# USB_Host_Hub_TypeC_DRP.net
KiCad netlist of a schematic drawn in Altium Designer
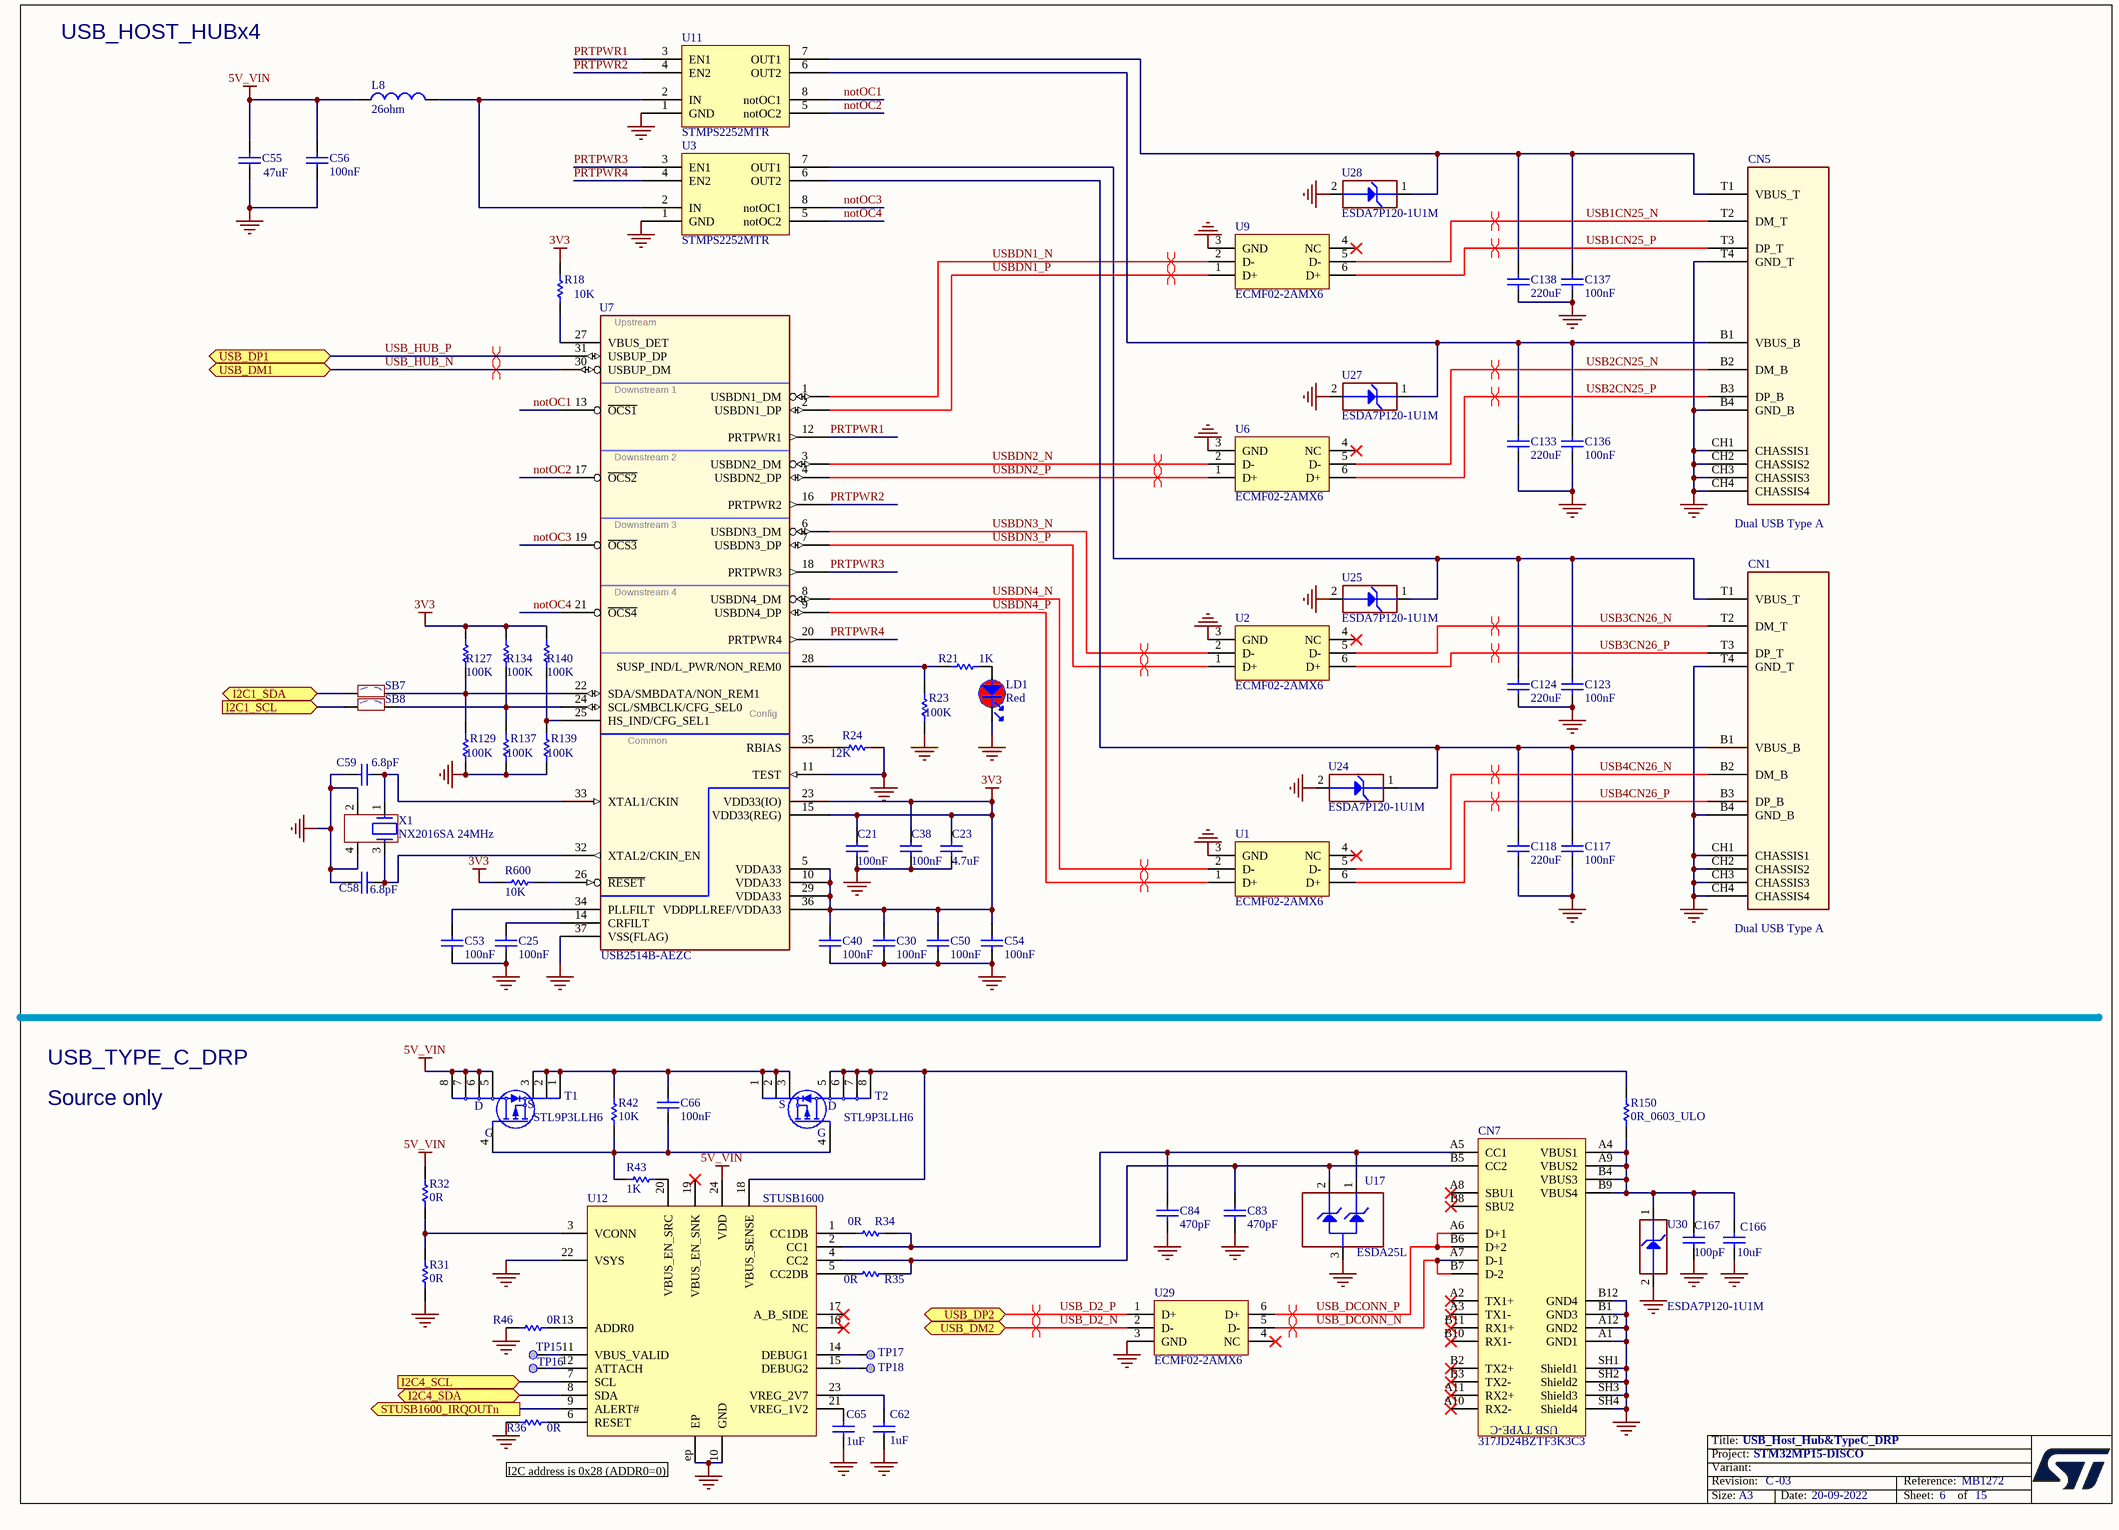
[diagram p0: USB_Host_Hub&TypeC_DRP.SchDoc]

(export (version "E")
  (design (tool "Eeschema 10.0.6"))
  (components
    (comp (ref "C21")
      (value "100nF")
      (footprint "C0402")
      (description "Capacitor, MLCC, 100nF, 16V, X7R, +/-10%, 0402, T=0.5mm")
      (fields
        (field (name "INTERNAL_PART_NUMBER") "MCD-00006")
        (field (name "MANUFACTURER_PART_NUMBER") "CC0402KRX7R7BB104")
      )
      (libsource (lib "MCD_PARTS_database") (part "Capacitor"))
    )
    (comp (ref "C23")
      (value "4.7uF")
      (footprint "C0402")
      (description "Capacitor, MLCC, 4.7uF, 6V3, X5R, 20%, 0402, T=0,5mm")
      (fields
        (field (name "INTERNAL_PART_NUMBER") "MCD-01356")
        (field (name "MANUFACTURER_PART_NUMBER") "GRM155R60J475ME47")
        (field (name "PROVIDED_BY") "SUBCO")
      )
      (libsource (lib "MCD_PARTS_database") (part "Capacitor"))
    )
    (comp (ref "C25")
      (value "100nF")
      (footprint "C0402")
      (description "Capacitor, MLCC, 100nF, 16V, X7R, +/-10%, 0402, T=0.5mm")
      (fields
        (field (name "INTERNAL_PART_NUMBER") "MCD-00006")
        (field (name "MANUFACTURER_PART_NUMBER") "CC0402KRX7R7BB104")
      )
      (libsource (lib "MCD_PARTS_database") (part "Capacitor"))
    )
    (comp (ref "C30")
      (value "100nF")
      (footprint "C0402")
      (description "Capacitor, MLCC, 100nF, 16V, X7R, +/-10%, 0402, T=0.5mm")
      (fields
        (field (name "INTERNAL_PART_NUMBER") "MCD-00006")
        (field (name "MANUFACTURER_PART_NUMBER") "CC0402KRX7R7BB104")
      )
      (libsource (lib "MCD_PARTS_database") (part "Capacitor"))
    )
    (comp (ref "C38")
      (value "100nF")
      (footprint "C0402")
      (description "Capacitor, MLCC, 100nF, 16V, X7R, +/-10%, 0402, T=0.5mm")
      (fields
        (field (name "INTERNAL_PART_NUMBER") "MCD-00006")
        (field (name "MANUFACTURER_PART_NUMBER") "CC0402KRX7R7BB104")
      )
      (libsource (lib "MCD_PARTS_database") (part "Capacitor"))
    )
    (comp (ref "C40")
      (value "100nF")
      (footprint "C0402")
      (description "Capacitor, MLCC, 100nF, 16V, X7R, +/-10%, 0402, T=0.5mm")
      (fields
        (field (name "INTERNAL_PART_NUMBER") "MCD-00006")
        (field (name "MANUFACTURER_PART_NUMBER") "CC0402KRX7R7BB104")
      )
      (libsource (lib "MCD_PARTS_database") (part "Capacitor"))
    )
    (comp (ref "C50")
      (value "100nF")
      (footprint "C0402")
      (description "Capacitor, MLCC, 100nF, 16V, X7R, +/-10%, 0402, T=0.5mm")
      (fields
        (field (name "INTERNAL_PART_NUMBER") "MCD-00006")
        (field (name "MANUFACTURER_PART_NUMBER") "CC0402KRX7R7BB104")
      )
      (libsource (lib "MCD_PARTS_database") (part "Capacitor"))
    )
    (comp (ref "C53")
      (value "100nF")
      (footprint "C0402")
      (description "Capacitor, MLCC, 100nF, 16V, X7R, +/-10%, 0402, T=0.5mm")
      (fields
        (field (name "INTERNAL_PART_NUMBER") "MCD-00006")
        (field (name "MANUFACTURER_PART_NUMBER") "CC0402KRX7R7BB104")
      )
      (libsource (lib "MCD_PARTS_database") (part "Capacitor"))
    )
    (comp (ref "C54")
      (value "100nF")
      (footprint "C0402")
      (description "Capacitor, MLCC, 100nF, 16V, X7R, +/-10%, 0402, T=0.5mm")
      (fields
        (field (name "INTERNAL_PART_NUMBER") "MCD-00006")
        (field (name "MANUFACTURER_PART_NUMBER") "CC0402KRX7R7BB104")
      )
      (libsource (lib "MCD_PARTS_database") (part "Capacitor"))
    )
    (comp (ref "C55")
      (value "47uF")
      (footprint "C0805")
      (description "Capacitor, MLCC, 47uF, 10V, X5R, 20%, 0805, T=1,25mm")
      (fields
        (field (name "INTERNAL_PART_NUMBER") "MCD-00204")
        (field (name "MANUFACTURER_PART_NUMBER") "GRM21BR61A476ME15K")
        (field (name "PROVIDED_BY") "SUBCO")
      )
      (libsource (lib "MCD_PARTS_database") (part "Capacitor"))
    )
    (comp (ref "C56")
      (value "100nF")
      (footprint "C0402")
      (description "Capacitor, MLCC, 100nF, 16V, X7R, +/-10%, 0402, T=0.5mm")
      (fields
        (field (name "INTERNAL_PART_NUMBER") "MCD-00006")
        (field (name "MANUFACTURER_PART_NUMBER") "CC0402KRX7R7BB104")
      )
      (libsource (lib "MCD_PARTS_database") (part "Capacitor"))
    )
    (comp (ref "C58")
      (value "6.8pF")
      (footprint "C0402")
      (description "Capacitor, MLCC, 6.8pF, 50V, NPO, +-0.25pF, 0402, T=0.5mm")
      (fields
        (field (name "INTERNAL_PART_NUMBER") "MCD-00674")
        (field (name "MANUFACTURER_PART_NUMBER") "CC0402CRNPO9BN6R8")
        (field (name "PROVIDED_BY") "SUBCO")
      )
      (libsource (lib "MCD_PARTS_database") (part "Capacitor"))
    )
    (comp (ref "C59")
      (value "6.8pF")
      (footprint "C0402")
      (description "Capacitor, MLCC, 6.8pF, 50V, NPO, +-0.25pF, 0402, T=0.5mm")
      (fields
        (field (name "INTERNAL_PART_NUMBER") "MCD-00674")
        (field (name "MANUFACTURER_PART_NUMBER") "CC0402CRNPO9BN6R8")
        (field (name "PROVIDED_BY") "SUBCO")
      )
      (libsource (lib "MCD_PARTS_database") (part "Capacitor"))
    )
    (comp (ref "C62")
      (value "1uF")
      (footprint "C0402")
      (description "Capacitor, MLCC, 1uF, 6V3, X5R, 10%, 0402, T=0,5mm")
      (fields
        (field (name "INTERNAL_PART_NUMBER") "MCD-00095")
        (field (name "MANUFACTURER_PART_NUMBER") "GRM155R61E105KA12")
        (field (name "PROVIDED_BY") "SUBCO")
      )
      (libsource (lib "MCD_PARTS_database") (part "Capacitor"))
    )
    (comp (ref "C65")
      (value "1uF")
      (footprint "C0402")
      (description "Capacitor, MLCC, 1uF, 6V3, X5R, 10%, 0402, T=0,5mm")
      (fields
        (field (name "INTERNAL_PART_NUMBER") "MCD-00095")
        (field (name "MANUFACTURER_PART_NUMBER") "GRM155R61E105KA12")
        (field (name "PROVIDED_BY") "SUBCO")
      )
      (libsource (lib "MCD_PARTS_database") (part "Capacitor"))
    )
    (comp (ref "C66")
      (value "100nF")
      (footprint "C0402")
      (description "Capacitor, MLCC, 100nF, 16V, X7R, +/-10%, 0402, T=0.5mm")
      (fields
        (field (name "INTERNAL_PART_NUMBER") "MCD-00006")
        (field (name "MANUFACTURER_PART_NUMBER") "CC0402KRX7R7BB104")
      )
      (libsource (lib "MCD_PARTS_database") (part "Capacitor"))
    )
    (comp (ref "C83")
      (value "470pF")
      (footprint "C0402")
      (description "Capacitor, MLCC, 470pF, 50V, NPO, 5%, 0402, T=0,5mm")
      (fields
        (field (name "INTERNAL_PART_NUMBER") "MCD-00724")
        (field (name "MANUFACTURER_PART_NUMBER") "CC0402JRNPO9BN471")
        (field (name "PROVIDED_BY") "SUBCO")
      )
      (libsource (lib "MCD_PARTS_database") (part "Capacitor"))
    )
    (comp (ref "C84")
      (value "470pF")
      (footprint "C0402")
      (description "Capacitor, MLCC, 470pF, 50V, NPO, 5%, 0402, T=0,5mm")
      (fields
        (field (name "INTERNAL_PART_NUMBER") "MCD-00724")
        (field (name "MANUFACTURER_PART_NUMBER") "CC0402JRNPO9BN471")
        (field (name "PROVIDED_BY") "SUBCO")
      )
      (libsource (lib "MCD_PARTS_database") (part "Capacitor"))
    )
    (comp (ref "C117")
      (value "100nF")
      (footprint "C0402")
      (description "Capacitor, MLCC, 100nF, 16V, X7R, +/-10%, 0402, T=0.5mm")
      (fields
        (field (name "INTERNAL_PART_NUMBER") "MCD-00006")
        (field (name "MANUFACTURER_PART_NUMBER") "CC0402KRX7R7BB104")
      )
      (libsource (lib "MCD_PARTS_database") (part "Capacitor"))
    )
    (comp (ref "C118")
      (value "220uF")
      (footprint "C1206_H1P6")
      (description "Capacitor, MLCC, 220uF, 6V3, X5R, 20%, 1206, T=1,6mm")
      (fields
        (field (name "INTERNAL_PART_NUMBER") "MCD-00104")
        (field (name "MANUFACTURER_PART_NUMBER") "GRM31CR60J227ME11")
        (field (name "PROVIDED_BY") "SUBCO")
      )
      (libsource (lib "MCD_PARTS_database") (part "Capacitor"))
    )
    (comp (ref "C123")
      (value "100nF")
      (footprint "C0402")
      (description "Capacitor, MLCC, 100nF, 16V, X7R, +/-10%, 0402, T=0.5mm")
      (fields
        (field (name "INTERNAL_PART_NUMBER") "MCD-00006")
        (field (name "MANUFACTURER_PART_NUMBER") "CC0402KRX7R7BB104")
      )
      (libsource (lib "MCD_PARTS_database") (part "Capacitor"))
    )
    (comp (ref "C124")
      (value "220uF")
      (footprint "C1206_H1P6")
      (description "Capacitor, MLCC, 220uF, 6V3, X5R, 20%, 1206, T=1,6mm")
      (fields
        (field (name "INTERNAL_PART_NUMBER") "MCD-00104")
        (field (name "MANUFACTURER_PART_NUMBER") "GRM31CR60J227ME11")
        (field (name "PROVIDED_BY") "SUBCO")
      )
      (libsource (lib "MCD_PARTS_database") (part "Capacitor"))
    )
    (comp (ref "C133")
      (value "220uF")
      (footprint "C1206_H1P6")
      (description "Capacitor, MLCC, 220uF, 6V3, X5R, 20%, 1206, T=1,6mm")
      (fields
        (field (name "INTERNAL_PART_NUMBER") "MCD-00104")
        (field (name "MANUFACTURER_PART_NUMBER") "GRM31CR60J227ME11")
        (field (name "PROVIDED_BY") "SUBCO")
      )
      (libsource (lib "MCD_PARTS_database") (part "Capacitor"))
    )
    (comp (ref "C136")
      (value "100nF")
      (footprint "C0402")
      (description "Capacitor, MLCC, 100nF, 16V, X7R, +/-10%, 0402, T=0.5mm")
      (fields
        (field (name "INTERNAL_PART_NUMBER") "MCD-00006")
        (field (name "MANUFACTURER_PART_NUMBER") "CC0402KRX7R7BB104")
      )
      (libsource (lib "MCD_PARTS_database") (part "Capacitor"))
    )
    (comp (ref "C137")
      (value "100nF")
      (footprint "C0402")
      (description "Capacitor, MLCC, 100nF, 16V, X7R, +/-10%, 0402, T=0.5mm")
      (fields
        (field (name "INTERNAL_PART_NUMBER") "MCD-00006")
        (field (name "MANUFACTURER_PART_NUMBER") "CC0402KRX7R7BB104")
      )
      (libsource (lib "MCD_PARTS_database") (part "Capacitor"))
    )
    (comp (ref "C138")
      (value "220uF")
      (footprint "C1206_H1P6")
      (description "Capacitor, MLCC, 220uF, 6V3, X5R, 20%, 1206, T=1,6mm")
      (fields
        (field (name "INTERNAL_PART_NUMBER") "MCD-00104")
        (field (name "MANUFACTURER_PART_NUMBER") "GRM31CR60J227ME11")
        (field (name "PROVIDED_BY") "SUBCO")
      )
      (libsource (lib "MCD_PARTS_database") (part "Capacitor"))
    )
    (comp (ref "C166")
      (value "10uF")
      (footprint "C0805")
      (description "Capacitor, MLCC, 10uF, 25V, X5R, 10%, 0805, T=0,85mm")
      (fields
        (field (name "INTERNAL_PART_NUMBER") "MCD-00014")
        (field (name "MANUFACTURER_PART_NUMBER") "CC0805KRX5R8BB106")
        (field (name "PROVIDED_BY") "SUBCO")
      )
      (libsource (lib "MCD_PARTS_database") (part "Capacitor"))
    )
    (comp (ref "C167")
      (value "100pF")
      (footprint "C0402")
      (description "Capacitor, MLCC, 100pF, 50V, NPO, 5%, 0402, T=0,5mm")
      (fields
        (field (name "INTERNAL_PART_NUMBER") "MCD-00205")
        (field (name "MANUFACTURER_PART_NUMBER") "CC0402JRNPO9BN101")
        (field (name "PROVIDED_BY") "SUBCO")
      )
      (libsource (lib "MCD_PARTS_database") (part "Capacitor"))
    )
    (comp (ref "CN1")
      (value "Dual USB Type A")
      (footprint "CON_DUAL-USB-TYPE-A_CONEXCON_5600-3081")
      (description "USB-Receptacle,Dual-Type-A, RA, TH, Height 15.5mm")
      (fields
        (field (name "INTERNAL_PART_NUMBER") "MCD-00109")
        (field (name "MANUFACTURER_PART_NUMBER") "5600-3081")
        (field (name "PROVIDED_BY") "SUBCO")
      )
      (libsource (lib "MCD_PARTS_database") (part "USB_DUAL_TYPEA_5600-3081"))
    )
    (comp (ref "CN5")
      (value "Dual USB Type A")
      (footprint "CON_DUAL-USB-TYPE-A_CONEXCON_5600-3081")
      (description "USB-Receptacle,Dual-Type-A, RA, TH, Height 15.5mm")
      (fields
        (field (name "INTERNAL_PART_NUMBER") "MCD-00109")
        (field (name "MANUFACTURER_PART_NUMBER") "5600-3081")
        (field (name "PROVIDED_BY") "SUBCO")
      )
      (libsource (lib "MCD_PARTS_database") (part "USB_DUAL_TYPEA_5600-3081"))
    )
    (comp (ref "CN7")
      (value "317JD24BZTF3K3C3")
      (footprint "CON_USB-TYPEC_COXOC_317JD24BZTF3K3C3")
      (description "USB tyce C certified receptacle for 1.6mm pcb height")
      (fields
        (field (name "INTERNAL_PART_NUMBER") "MCD-01108")
        (field (name "MANUFACTURER") "CHANT SINCERE (COXOC)")
        (field (name "PROVIDED_BY") "SUBCO")
      )
      (libsource (lib "MCD_PARTS_database") (part "USB_TYPE_C_Receptacle_317JD24BZTF3K3C3"))
    )
    (comp (ref "L8")
      (value "26ohm")
      (footprint "FIL_0603_H0P65")
      (description "Bead,26R at 100Mhz,6A,0603")
      (fields
        (field (name "INTERNAL_PART_NUMBER") "MCD-00305")
        (field (name "MANUFACTURER_PART_NUMBER") "BLM18KG260TN1")
        (field (name "PROVIDED_BY") "SUBCO")
      )
      (libsource (lib "MCD_PARTS_database") (part "BEAD"))
    )
    (comp (ref "LD1")
      (value "Red")
      (footprint "LED_0603_RED")
      (description "LED, Red, 2V35, 20mA, 0603")
      (fields (field (name "INTERNAL_PART_NUMBER") "MCD-02899") (field (name "MANUFACTURER") "EVERLIGHT"))
      (libsource (lib "MCD_PARTS_database") (part "LED_red"))
    )
    (comp (ref "R18")
      (value "10K")
      (footprint "R0402")
      (description "Resistor,10K,0402,1%,1/16W")
      (fields
        (field (name "INTERNAL_PART_NUMBER") "MCD-00053")
        (field (name "MANUFACTURER_PART_NUMBER") "RC0402FR-0710KL")
        (field (name "PROVIDED_BY") "SUBCO")
      )
      (libsource (lib "MCD_PARTS_database") (part "Resistor"))
    )
    (comp (ref "R21")
      (value "1K")
      (footprint "R0402")
      (description "Resistor,1K,0402,1%,1/16W")
      (fields
        (field (name "INTERNAL_PART_NUMBER") "MCD-00061")
        (field (name "MANUFACTURER_PART_NUMBER") "RC0402FR-071KL")
        (field (name "PROVIDED_BY") "SUBCO")
      )
      (libsource (lib "MCD_PARTS_database") (part "Resistor"))
    )
    (comp (ref "R23")
      (value "100K")
      (footprint "R0402")
      (description "Resistor,100K,0402,1%,1/16W")
      (fields
        (field (name "INTERNAL_PART_NUMBER") "MCD-00059")
        (field (name "MANUFACTURER_PART_NUMBER") "RC0402FR-07100KL")
        (field (name "PROVIDED_BY") "SUBCO")
      )
      (libsource (lib "MCD_PARTS_database") (part "Resistor"))
    )
    (comp (ref "R24")
      (value "12K")
      (footprint "R0402")
      (description "Resistor,12K,0402,1%,1/16W")
      (fields
        (field (name "INTERNAL_PART_NUMBER") "MCD-00187")
        (field (name "MANUFACTURER_PART_NUMBER") "RC0402FR-0712KL")
        (field (name "PROVIDED_BY") "SUBCO")
      )
      (libsource (lib "MCD_PARTS_database") (part "Resistor"))
    )
    (comp (ref "R31")
      (value "0R")
      (footprint "R0402")
      (description "Resistor,0R,0402,5%,1/16W")
      (fields
        (field (name "INTERNAL_PART_NUMBER") "MCD-00052")
        (field (name "MANUFACTURER_PART_NUMBER") "RC0402JR-070RL")
        (field (name "PROVIDED_BY") "SUBCO")
      )
      (libsource (lib "MCD_PARTS_database") (part "Resistor"))
    )
    (comp (ref "R32")
      (value "0R")
      (footprint "R0402")
      (description "Resistor,0R,0402,5%,1/16W")
      (fields
        (field (name "INTERNAL_PART_NUMBER") "MCD-00052")
        (field (name "MANUFACTURER_PART_NUMBER") "RC0402JR-070RL")
        (field (name "PROVIDED_BY") "SUBCO")
      )
      (libsource (lib "MCD_PARTS_database") (part "Resistor"))
    )
    (comp (ref "R34")
      (value "0R")
      (footprint "R0402")
      (description "Resistor,0R,0402,5%,1/16W")
      (fields
        (field (name "INTERNAL_PART_NUMBER") "MCD-00052")
        (field (name "MANUFACTURER_PART_NUMBER") "RC0402JR-070RL")
        (field (name "PROVIDED_BY") "SUBCO")
      )
      (libsource (lib "MCD_PARTS_database") (part "Resistor"))
    )
    (comp (ref "R35")
      (value "0R")
      (footprint "R0402")
      (description "Resistor,0R,0402,5%,1/16W")
      (fields
        (field (name "INTERNAL_PART_NUMBER") "MCD-00052")
        (field (name "MANUFACTURER_PART_NUMBER") "RC0402JR-070RL")
        (field (name "PROVIDED_BY") "SUBCO")
      )
      (libsource (lib "MCD_PARTS_database") (part "Resistor"))
    )
    (comp (ref "R36")
      (value "0R")
      (footprint "R0402")
      (description "Resistor,0R,0402,5%,1/16W")
      (fields
        (field (name "INTERNAL_PART_NUMBER") "MCD-00052")
        (field (name "MANUFACTURER_PART_NUMBER") "RC0402JR-070RL")
        (field (name "PROVIDED_BY") "SUBCO")
      )
      (libsource (lib "MCD_PARTS_database") (part "Resistor"))
    )
    (comp (ref "R42")
      (value "10K")
      (footprint "R0402")
      (description "Resistor,10K,0402,1%,1/16W")
      (fields
        (field (name "INTERNAL_PART_NUMBER") "MCD-00053")
        (field (name "MANUFACTURER_PART_NUMBER") "RC0402FR-0710KL")
        (field (name "PROVIDED_BY") "SUBCO")
      )
      (libsource (lib "MCD_PARTS_database") (part "Resistor"))
    )
    (comp (ref "R43")
      (value "1K")
      (footprint "R0402")
      (description "Resistor,1K,0402,1%,1/16W")
      (fields
        (field (name "INTERNAL_PART_NUMBER") "MCD-00061")
        (field (name "MANUFACTURER_PART_NUMBER") "RC0402FR-071KL")
        (field (name "PROVIDED_BY") "SUBCO")
      )
      (libsource (lib "MCD_PARTS_database") (part "Resistor"))
    )
    (comp (ref "R46")
      (value "0R")
      (footprint "R0402")
      (description "Resistor,0R,0402,5%,1/16W")
      (fields
        (field (name "INTERNAL_PART_NUMBER") "MCD-00052")
        (field (name "MANUFACTURER_PART_NUMBER") "RC0402JR-070RL")
        (field (name "PROVIDED_BY") "SUBCO")
      )
      (libsource (lib "MCD_PARTS_database") (part "Resistor"))
    )
    (comp (ref "R127")
      (value "100K")
      (footprint "R0402")
      (description "Resistor,100K,0402,1%,1/16W")
      (fields
        (field (name "INTERNAL_PART_NUMBER") "MCD-00059")
        (field (name "MANUFACTURER_PART_NUMBER") "RC0402FR-07100KL")
        (field (name "PROVIDED_BY") "SUBCO")
      )
      (libsource (lib "MCD_PARTS_database") (part "Resistor"))
    )
    (comp (ref "R129")
      (value "100K")
      (footprint "R0402")
      (description "Resistor,100K,0402,1%,1/16W")
      (fields
        (field (name "INTERNAL_PART_NUMBER") "MCD-00059")
        (field (name "MANUFACTURER_PART_NUMBER") "RC0402FR-07100KL")
        (field (name "PROVIDED_BY") "SUBCO")
      )
      (libsource (lib "MCD_PARTS_database") (part "Resistor"))
    )
    (comp (ref "R134")
      (value "100K")
      (footprint "R0402")
      (description "Resistor,100K,0402,1%,1/16W")
      (fields
        (field (name "INTERNAL_PART_NUMBER") "MCD-00059")
        (field (name "MANUFACTURER_PART_NUMBER") "RC0402FR-07100KL")
        (field (name "PROVIDED_BY") "SUBCO")
      )
      (libsource (lib "MCD_PARTS_database") (part "Resistor"))
    )
    (comp (ref "R137")
      (value "100K")
      (footprint "R0402")
      (description "Resistor,100K,0402,1%,1/16W")
      (fields
        (field (name "INTERNAL_PART_NUMBER") "MCD-00059")
        (field (name "MANUFACTURER_PART_NUMBER") "RC0402FR-07100KL")
        (field (name "PROVIDED_BY") "SUBCO")
      )
      (libsource (lib "MCD_PARTS_database") (part "Resistor"))
    )
    (comp (ref "R139")
      (value "100K")
      (footprint "R0402")
      (description "Resistor,100K,0402,1%,1/16W")
      (fields
        (field (name "INTERNAL_PART_NUMBER") "MCD-00059")
        (field (name "MANUFACTURER_PART_NUMBER") "RC0402FR-07100KL")
        (field (name "PROVIDED_BY") "SUBCO")
      )
      (libsource (lib "MCD_PARTS_database") (part "Resistor"))
    )
    (comp (ref "R140")
      (value "100K")
      (footprint "R0402")
      (description "Resistor,100K,0402,1%,1/16W")
      (fields
        (field (name "INTERNAL_PART_NUMBER") "MCD-00059")
        (field (name "MANUFACTURER_PART_NUMBER") "RC0402FR-07100KL")
        (field (name "PROVIDED_BY") "SUBCO")
      )
      (libsource (lib "MCD_PARTS_database") (part "Resistor"))
    )
    (comp (ref "R150")
      (value "0R_0603_ULO")
      (footprint "R0603")
      (description "Resistor,0R,0603,ULO")
      (fields
        (field (name "INTERNAL_PART_NUMBER") "MCD-00181")
        (field (name "MANUFACTURER_PART_NUMBER") "PMR03EZPJ000")
        (field (name "PROVIDED_BY") "SUBCO")
      )
      (libsource (lib "MCD_PARTS_database") (part "Resistor"))
    )
    (comp (ref "R600")
      (value "10K")
      (footprint "R0402")
      (description "Resistor,10K,0402,1%,1/16W")
      (fields
        (field (name "INTERNAL_PART_NUMBER") "MCD-00053")
        (field (name "MANUFACTURER_PART_NUMBER") "RC0402FR-0710KL")
        (field (name "PROVIDED_BY") "SUBCO")
      )
      (libsource (lib "MCD_PARTS_database") (part "Resistor"))
    )
    (comp (ref "SB7")
      (value "SB_OFF")
      (footprint "SOLDER-BRIDGE_R0603-0R")
      (description "Solder Bridge OFF")
      (fields
        (field (name "INTERNAL_PART_NUMBER") "MCD-00072")
        (field (name "MANUFACTURER") "YAGEO")
        (field (name "PROVIDED_BY") "SUBCO")
      )
      (libsource (lib "MCD_PARTS_database") (part "SB_OFF"))
    )
    (comp (ref "SB8")
      (value "SB_OFF")
      (footprint "SOLDER-BRIDGE_R0603-0R")
      (description "Solder Bridge OFF")
      (fields
        (field (name "INTERNAL_PART_NUMBER") "MCD-00072")
        (field (name "MANUFACTURER") "YAGEO")
        (field (name "PROVIDED_BY") "SUBCO")
      )
      (libsource (lib "MCD_PARTS_database") (part "SB_OFF"))
    )
    (comp (ref "T1")
      (value "STL9P3LLH6")
      (footprint "MOS_POWERFLAT_3P3X3P3_P065")
      (description "Power Mosfet, P-channel,VDS -30V,RDS 12mohm typ,ID -9A")
      (fields
        (field (name "INTERNAL_PART_NUMBER") "MCD-01126")
        (field (name "MANUFACTURER") "STMICROELECTRONICS")
        (field (name "PROVIDED_BY") "SUBCO with ST control")
      )
      (libsource (lib "MCD_PARTS_database") (part "STL9P3LLH6"))
    )
    (comp (ref "T2")
      (value "STL9P3LLH6")
      (footprint "MOS_POWERFLAT_3P3X3P3_P065")
      (description "Power Mosfet, P-channel,VDS -30V,RDS 12mohm typ,ID -9A")
      (fields
        (field (name "INTERNAL_PART_NUMBER") "MCD-01126")
        (field (name "MANUFACTURER") "STMICROELECTRONICS")
        (field (name "PROVIDED_BY") "SUBCO with ST control")
      )
      (libsource (lib "MCD_PARTS_database") (part "STL9P3LLH6"))
    )
    (comp (ref "TP15")
      (value "Test Point")
      (footprint "TP_SMD_1MM")
      (description "Test Point 1mm")
      (fields
        (field (name "INTERNAL_PART_NUMBER") "MCD-00074")
        (field (name "MANUFACTURER_PART_NUMBER") "n/a")
      )
      (libsource (lib "") (part "Test Point_1"))
    )
    (comp (ref "TP16")
      (value "Test Point")
      (footprint "TP_SMD_1MM")
      (description "Test Point 1mm")
      (fields
        (field (name "INTERNAL_PART_NUMBER") "MCD-00074")
        (field (name "MANUFACTURER_PART_NUMBER") "n/a")
      )
      (libsource (lib "") (part "Test Point_1"))
    )
    (comp (ref "TP17")
      (value "Test Point")
      (footprint "TP_SMD_1MM")
      (description "Test Point 1mm")
      (fields
        (field (name "INTERNAL_PART_NUMBER") "MCD-00074")
        (field (name "MANUFACTURER_PART_NUMBER") "n/a")
      )
      (libsource (lib "MCD_PARTS_database") (part "Test Point"))
    )
    (comp (ref "TP18")
      (value "Test Point")
      (footprint "TP_SMD_1MM")
      (description "Test Point 1mm")
      (fields
        (field (name "INTERNAL_PART_NUMBER") "MCD-00074")
        (field (name "MANUFACTURER_PART_NUMBER") "n/a")
      )
      (libsource (lib "MCD_PARTS_database") (part "Test Point"))
    )
    (comp (ref "U1")
      (value "ECMF02-2AMX6")
      (footprint "ESD_QFN-6L_1P7X1P5_P050")
      (description "Common mode filter with ESD protection for USB 2.0 interface")
      (fields
        (field (name "INTERNAL_PART_NUMBER") "MCD-00649")
        (field (name "MANUFACTURER") "STMICROELECTRONICS")
        (field (name "PROVIDED_BY") "SUBCO with ST control")
      )
      (libsource (lib "") (part "ECMF02-2AMX6_1"))
    )
    (comp (ref "U2")
      (value "ECMF02-2AMX6")
      (footprint "ESD_QFN-6L_1P7X1P5_P050")
      (description "Common mode filter with ESD protection for USB 2.0 interface")
      (fields
        (field (name "INTERNAL_PART_NUMBER") "MCD-00649")
        (field (name "MANUFACTURER") "STMICROELECTRONICS")
        (field (name "PROVIDED_BY") "SUBCO with ST control")
      )
      (libsource (lib "") (part "ECMF02-2AMX6_1"))
    )
    (comp (ref "U3")
      (value "STMPS2252MTR")
      (footprint "ICC_SO8_5X4_P127")
      (description "IC,Dual-Channel-Power-Switch,500mA,100mR,SO8")
      (fields
        (field (name "INTERNAL_PART_NUMBER") "MCD-00123")
        (field (name "MANUFACTURER") "STMICROELECTRONICS")
        (field (name "PROVIDED_BY") "SUBCO with ST control")
      )
      (libsource (lib "MCD_PARTS_database") (part "STMPS2252MTR"))
    )
    (comp (ref "U6")
      (value "ECMF02-2AMX6")
      (footprint "ESD_QFN-6L_1P7X1P5_P050")
      (description "Common mode filter with ESD protection for USB 2.0 interface")
      (fields
        (field (name "INTERNAL_PART_NUMBER") "MCD-00649")
        (field (name "MANUFACTURER") "STMICROELECTRONICS")
        (field (name "PROVIDED_BY") "SUBCO with ST control")
      )
      (libsource (lib "") (part "ECMF02-2AMX6_1"))
    )
    (comp (ref "U7")
      (value "USB2514B-AEZC")
      (footprint "ICC_QFN36-EPAD_6X6_P050")
      (description "USB HUB 2,0 Controller")
      (fields
        (field (name "INTERNAL_PART_NUMBER") "MCD-00145")
        (field (name "MANUFACTURER") "MICROCHIP")
        (field (name "PROVIDED_BY") "SUBCO")
      )
      (libsource (lib "MCD_PARTS_database") (part "USB2514B-AEZC"))
    )
    (comp (ref "U9")
      (value "ECMF02-2AMX6")
      (footprint "ESD_QFN-6L_1P7X1P5_P050")
      (description "Common mode filter with ESD protection for USB 2.0 interface")
      (fields
        (field (name "INTERNAL_PART_NUMBER") "MCD-00649")
        (field (name "MANUFACTURER") "STMICROELECTRONICS")
        (field (name "PROVIDED_BY") "SUBCO with ST control")
      )
      (libsource (lib "") (part "ECMF02-2AMX6_1"))
    )
    (comp (ref "U11")
      (value "STMPS2252MTR")
      (footprint "ICC_SO8_5X4_P127")
      (description "IC,Dual-Channel-Power-Switch,500mA,100mR,SO8")
      (fields
        (field (name "INTERNAL_PART_NUMBER") "MCD-00123")
        (field (name "MANUFACTURER") "STMICROELECTRONICS")
        (field (name "PROVIDED_BY") "SUBCO with ST control")
      )
      (libsource (lib "MCD_PARTS_database") (part "STMPS2252MTR"))
    )
    (comp (ref "U12")
      (value "STUSB1600")
      (footprint "ICC_QFN24-EPAD_4X4_P050")
      (description "USB Type-C controller with VCONN switch")
      (fields
        (field (name "INTERNAL_PART_NUMBER") "MCD-00676")
        (field (name "MANUFACTURER_PART_NUMBER") "STUSB1600AQTR")
        (field (name "PROVIDED_BY") "SUBCO with ST control")
      )
      (libsource (lib "MCD_PARTS_database") (part "STUSB1600QTR"))
    )
    (comp (ref "U17")
      (value "ESDA25L")
      (footprint "ESD_SOT23")
      (description "DUAL TRANSIL ARRAY FOR ESD PROTECTION")
      (fields
        (field (name "INTERNAL_PART_NUMBER") "MCD-01125")
        (field (name "MANUFACTURER") "STMICROELECTRONICS")
        (field (name "PROVIDED_BY") "SUBCO with ST control")
      )
      (libsource (lib "MCD_PARTS_database") (part "ESDA25L"))
    )
    (comp (ref "U24")
      (value "ESDA7P120-1U1M")
      (footprint "ESD_QFN1610_2N_1K_2A")
      (description "High power transient voltage suppressor")
      (fields
        (field (name "INTERNAL_PART_NUMBER") "MCD-01026")
        (field (name "MANUFACTURER") "STMICROELECTRONICS")
        (field (name "PROVIDED_BY") "SUBCO with ST control")
      )
      (libsource (lib "MCD_PARTS_database") (part "ESD-TRANSIL"))
    )
    (comp (ref "U25")
      (value "ESDA7P120-1U1M")
      (footprint "ESD_QFN1610_2N_1K_2A")
      (description "High power transient voltage suppressor")
      (fields
        (field (name "INTERNAL_PART_NUMBER") "MCD-01026")
        (field (name "MANUFACTURER") "STMICROELECTRONICS")
        (field (name "PROVIDED_BY") "SUBCO with ST control")
      )
      (libsource (lib "MCD_PARTS_database") (part "ESD-TRANSIL"))
    )
    (comp (ref "U27")
      (value "ESDA7P120-1U1M")
      (footprint "ESD_QFN1610_2N_1K_2A")
      (description "High power transient voltage suppressor")
      (fields
        (field (name "INTERNAL_PART_NUMBER") "MCD-01026")
        (field (name "MANUFACTURER") "STMICROELECTRONICS")
        (field (name "PROVIDED_BY") "SUBCO with ST control")
      )
      (libsource (lib "MCD_PARTS_database") (part "ESD-TRANSIL"))
    )
    (comp (ref "U28")
      (value "ESDA7P120-1U1M")
      (footprint "ESD_QFN1610_2N_1K_2A")
      (description "High power transient voltage suppressor")
      (fields
        (field (name "INTERNAL_PART_NUMBER") "MCD-01026")
        (field (name "MANUFACTURER") "STMICROELECTRONICS")
        (field (name "PROVIDED_BY") "SUBCO with ST control")
      )
      (libsource (lib "MCD_PARTS_database") (part "ESD-TRANSIL"))
    )
    (comp (ref "U29")
      (value "ECMF02-2AMX6")
      (footprint "ESD_QFN-6L_1P7X1P5_P050")
      (description "Common mode filter with ESD protection for USB 2.0 interface")
      (fields
        (field (name "INTERNAL_PART_NUMBER") "MCD-00649")
        (field (name "MANUFACTURER") "STMICROELECTRONICS")
        (field (name "PROVIDED_BY") "SUBCO with ST control")
      )
      (libsource (lib "MCD_PARTS_database") (part "ECMF02-2AMX6"))
    )
    (comp (ref "U30")
      (value "ESDA7P120-1U1M")
      (footprint "ESD_QFN1610_2N_1K_2A")
      (description "High power transient voltage suppressor")
      (fields
        (field (name "INTERNAL_PART_NUMBER") "MCD-01026")
        (field (name "MANUFACTURER") "STMICROELECTRONICS")
        (field (name "PROVIDED_BY") "SUBCO with ST control")
      )
      (libsource (lib "") (part "ESD-TRANSIL_1"))
    )
    (comp (ref "X1")
      (value "NX2016SA 24MHz")
      (footprint "CRY_NX2016SA_4P")
      (description "Crystal 24MHz, 6pF, +-20ppm, 80ohms max, SMD")
      (fields
        (field (name "INTERNAL_PART_NUMBER") "MCD-01036")
        (field (name "MANUFACTURER_PART_NUMBER") "NX2016SA 24MHz EXS00A-CS10820")
        (field (name "PROVIDED_BY") "SUBCO")
      )
      (libsource (lib "MCD_PARTS_database") (part "XTAL_4_PINS"))
    )
  )
  (nets
    (net (code "1") (name "/I2C1_SCL") (class "Default")
      (node (ref "SB8") (pin "1") (pinfunction "1_1") (pintype "passive"))
    )
    (net (code "2") (name "/I2C1_SDA") (class "Default")
      (node (ref "SB7") (pin "1") (pinfunction "1_1") (pintype "passive"))
    )
    (net (code "3") (name "/I2C4_SCL") (class "Default")
      (node (ref "U12") (pin "7") (pinfunction "SCL_7") (pintype "passive"))
    )
    (net (code "4") (name "/I2C4_SDA") (class "Default")
      (node (ref "U12") (pin "8") (pinfunction "SDA_8") (pintype "passive"))
    )
    (net (code "5") (name "/PRTPWR1") (class "Default")
      (node (ref "U11") (pin "3") (pinfunction "EN1_3") (pintype "passive"))
      (node (ref "U7") (pin "12") (pinfunction "PRTPWR1_12") (pintype "output"))
    )
    (net (code "6") (name "/PRTPWR2") (class "Default")
      (node (ref "U11") (pin "4") (pinfunction "EN2_4") (pintype "passive"))
      (node (ref "U7") (pin "16") (pinfunction "PRTPWR2_16") (pintype "output"))
    )
    (net (code "7") (name "/PRTPWR3") (class "Default")
      (node (ref "U3") (pin "3") (pinfunction "EN1_3") (pintype "passive"))
      (node (ref "U7") (pin "18") (pinfunction "PRTPWR3_18") (pintype "output"))
    )
    (net (code "8") (name "/PRTPWR4") (class "Default")
      (node (ref "U3") (pin "4") (pinfunction "EN2_4") (pintype "passive"))
      (node (ref "U7") (pin "20") (pinfunction "PRTPWR4_20") (pintype "output"))
    )
    (net (code "9") (name "/STUSB1600_IRQOUTn") (class "Default")
      (node (ref "U12") (pin "9") (pinfunction "ALERT#_9") (pintype "passive"))
    )
    (net (code "10") (name "/USB1CN25_N") (class "Default")
      (node (ref "CN5") (pin "T2") (pinfunction "DM_T_T2") (pintype "passive"))
      (node (ref "U9") (pin "5") (pinfunction "D-_5") (pintype "passive"))
    )
    (net (code "11") (name "/USB1CN25_P") (class "Default")
      (node (ref "CN5") (pin "T3") (pinfunction "DP_T_T3") (pintype "passive"))
      (node (ref "U9") (pin "6") (pinfunction "D+_6") (pintype "passive"))
    )
    (net (code "12") (name "/USB2CN25_N") (class "Default")
      (node (ref "CN5") (pin "B2") (pinfunction "DM_B_B2") (pintype "passive"))
      (node (ref "U6") (pin "5") (pinfunction "D-_5") (pintype "passive"))
    )
    (net (code "13") (name "/USB2CN25_P") (class "Default")
      (node (ref "CN5") (pin "B3") (pinfunction "DP_B_B3") (pintype "passive"))
      (node (ref "U6") (pin "6") (pinfunction "D+_6") (pintype "passive"))
    )
    (net (code "14") (name "/USB3CN26_N") (class "Default")
      (node (ref "CN1") (pin "T2") (pinfunction "DM_T_T2") (pintype "passive"))
      (node (ref "U2") (pin "5") (pinfunction "D-_5") (pintype "passive"))
    )
    (net (code "15") (name "/USB3CN26_P") (class "Default")
      (node (ref "CN1") (pin "T3") (pinfunction "DP_T_T3") (pintype "passive"))
      (node (ref "U2") (pin "6") (pinfunction "D+_6") (pintype "passive"))
    )
    (net (code "16") (name "/USB4CN26_N") (class "Default")
      (node (ref "CN1") (pin "B2") (pinfunction "DM_B_B2") (pintype "passive"))
      (node (ref "U1") (pin "5") (pinfunction "D-_5") (pintype "passive"))
    )
    (net (code "17") (name "/USB4CN26_P") (class "Default")
      (node (ref "CN1") (pin "B3") (pinfunction "DP_B_B3") (pintype "passive"))
      (node (ref "U1") (pin "6") (pinfunction "D+_6") (pintype "passive"))
    )
    (net (code "18") (name "/USBDN1_N") (class "Default")
      (node (ref "U7") (pin "1") (pinfunction "USBDN1_DM_1") (pintype "bidirectional"))
      (node (ref "U9") (pin "2") (pinfunction "D-_2") (pintype "passive"))
    )
    (net (code "19") (name "/USBDN1_P") (class "Default")
      (node (ref "U7") (pin "2") (pinfunction "USBDN1_DP_2") (pintype "bidirectional"))
      (node (ref "U9") (pin "1") (pinfunction "D+_1") (pintype "passive"))
    )
    (net (code "20") (name "/USBDN2_N") (class "Default")
      (node (ref "U6") (pin "2") (pinfunction "D-_2") (pintype "passive"))
      (node (ref "U7") (pin "3") (pinfunction "USBDN2_DM_3") (pintype "bidirectional"))
    )
    (net (code "21") (name "/USBDN2_P") (class "Default")
      (node (ref "U6") (pin "1") (pinfunction "D+_1") (pintype "passive"))
      (node (ref "U7") (pin "4") (pinfunction "USBDN2_DP_4") (pintype "bidirectional"))
    )
    (net (code "22") (name "/USBDN3_N") (class "Default")
      (node (ref "U2") (pin "2") (pinfunction "D-_2") (pintype "passive"))
      (node (ref "U7") (pin "6") (pinfunction "USBDN3_DM_6") (pintype "bidirectional"))
    )
    (net (code "23") (name "/USBDN3_P") (class "Default")
      (node (ref "U2") (pin "1") (pinfunction "D+_1") (pintype "passive"))
      (node (ref "U7") (pin "7") (pinfunction "USBDN3_DP_7") (pintype "bidirectional"))
    )
    (net (code "24") (name "/USBDN4_N") (class "Default")
      (node (ref "U1") (pin "2") (pinfunction "D-_2") (pintype "passive"))
      (node (ref "U7") (pin "8") (pinfunction "USBDN4_DM_8") (pintype "bidirectional"))
    )
    (net (code "25") (name "/USBDN4_P") (class "Default")
      (node (ref "U1") (pin "1") (pinfunction "D+_1") (pintype "passive"))
      (node (ref "U7") (pin "9") (pinfunction "USBDN4_DP_9") (pintype "bidirectional"))
    )
    (net (code "26") (name "/USB_D2_N") (class "Default")
      (node (ref "U29") (pin "2") (pinfunction "D-_2") (pintype "passive"))
    )
    (net (code "27") (name "/USB_D2_P") (class "Default")
      (node (ref "U29") (pin "1") (pinfunction "D+_1") (pintype "passive"))
    )
    (net (code "28") (name "/USB_DCONN_N") (class "Default")
      (node (ref "CN7") (pin "A7") (pinfunction "D-1_A7") (pintype "passive"))
      (node (ref "CN7") (pin "B7") (pinfunction "D-2_B7") (pintype "passive"))
      (node (ref "U29") (pin "5") (pinfunction "D-_5") (pintype "passive"))
    )
    (net (code "29") (name "/USB_DCONN_P") (class "Default")
      (node (ref "CN7") (pin "A6") (pinfunction "D+1_A6") (pintype "passive"))
      (node (ref "CN7") (pin "B6") (pinfunction "D+2_B6") (pintype "passive"))
      (node (ref "U29") (pin "6") (pinfunction "D+_6") (pintype "passive"))
    )
    (net (code "30") (name "/USB_HUB_N") (class "Default")
      (node (ref "U7") (pin "30") (pinfunction "USBUP_DM_30") (pintype "bidirectional"))
    )
    (net (code "31") (name "/USB_HUB_P") (class "Default")
      (node (ref "U7") (pin "31") (pinfunction "USBUP_DP_31") (pintype "bidirectional"))
    )
    (net (code "32") (name "/notOC1") (class "Default")
      (node (ref "U11") (pin "8") (pinfunction "notOC1_8") (pintype "passive"))
      (node (ref "U7") (pin "13") (pinfunction "~{OCS1}_13") (pintype "passive"))
    )
    (net (code "33") (name "/notOC2") (class "Default")
      (node (ref "U11") (pin "5") (pinfunction "notOC2_5") (pintype "passive"))
      (node (ref "U7") (pin "17") (pinfunction "~{OCS2}_17") (pintype "passive"))
    )
    (net (code "34") (name "/notOC3") (class "Default")
      (node (ref "U3") (pin "8") (pinfunction "notOC1_8") (pintype "passive"))
      (node (ref "U7") (pin "19") (pinfunction "~{OCS3}_19") (pintype "passive"))
    )
    (net (code "35") (name "/notOC4") (class "Default")
      (node (ref "U3") (pin "5") (pinfunction "notOC2_5") (pintype "passive"))
      (node (ref "U7") (pin "21") (pinfunction "~{OCS4}_21") (pintype "passive"))
    )
    (net (code "36") (name "3V3") (class "Default")
      (node (ref "C21") (pin "2") (pinfunction "2_2") (pintype "passive"))
      (node (ref "C23") (pin "2") (pinfunction "2_2") (pintype "passive"))
      (node (ref "C30") (pin "2") (pinfunction "2_2") (pintype "passive"))
      (node (ref "C38") (pin "2") (pinfunction "2_2") (pintype "passive"))
      (node (ref "C40") (pin "2") (pinfunction "2_2") (pintype "passive"))
      (node (ref "C50") (pin "2") (pinfunction "2_2") (pintype "passive"))
      (node (ref "C54") (pin "2") (pinfunction "2_2") (pintype "passive"))
      (node (ref "R127") (pin "2") (pinfunction "2_2") (pintype "passive"))
      (node (ref "R134") (pin "2") (pinfunction "2_2") (pintype "passive"))
      (node (ref "R140") (pin "2") (pinfunction "2_2") (pintype "passive"))
      (node (ref "R18") (pin "2") (pinfunction "2_2") (pintype "passive"))
      (node (ref "R600") (pin "1") (pinfunction "1_1") (pintype "passive"))
      (node (ref "U7") (pin "10") (pinfunction "VDDA33_10") (pintype "power_in"))
      (node (ref "U7") (pin "15") (pinfunction "VDD33(REG)_15") (pintype "power_in"))
      (node (ref "U7") (pin "23") (pinfunction "VDD33(IO)_23") (pintype "power_in"))
      (node (ref "U7") (pin "29") (pinfunction "VDDA33_29") (pintype "power_in"))
      (node (ref "U7") (pin "36") (pinfunction "VDDPLLREF/VDDA33_36") (pintype "power_in"))
      (node (ref "U7") (pin "5") (pinfunction "VDDA33_5") (pintype "power_in"))
    )
    (net (code "37") (name "5V_VIN") (class "Default")
      (node (ref "C55") (pin "2") (pinfunction "2_2") (pintype "passive"))
      (node (ref "C56") (pin "2") (pinfunction "2_2") (pintype "passive"))
      (node (ref "L8") (pin "1") (pinfunction "1_1") (pintype "passive"))
      (node (ref "R32") (pin "2") (pinfunction "2_2") (pintype "passive"))
      (node (ref "T1") (pin "5") (pinfunction "D_5") (pintype "passive"))
      (node (ref "T1") (pin "6") (pinfunction "D_6") (pintype "passive"))
      (node (ref "T1") (pin "7") (pinfunction "D_7") (pintype "passive"))
      (node (ref "T1") (pin "8") (pinfunction "D_8") (pintype "passive"))
      (node (ref "U12") (pin "24") (pinfunction "VDD_24") (pintype "passive"))
    )
    (net (code "38") (name "GND") (class "Default")
      (node (ref "C117") (pin "1") (pinfunction "1_1") (pintype "passive"))
      (node (ref "C118") (pin "1") (pinfunction "1_1") (pintype "passive"))
      (node (ref "C123") (pin "1") (pinfunction "1_1") (pintype "passive"))
      (node (ref "C124") (pin "1") (pinfunction "1_1") (pintype "passive"))
      (node (ref "C133") (pin "1") (pinfunction "1_1") (pintype "passive"))
      (node (ref "C136") (pin "1") (pinfunction "1_1") (pintype "passive"))
      (node (ref "C137") (pin "1") (pinfunction "1_1") (pintype "passive"))
      (node (ref "C138") (pin "1") (pinfunction "1_1") (pintype "passive"))
      (node (ref "C166") (pin "1") (pinfunction "1_1") (pintype "passive"))
      (node (ref "C167") (pin "1") (pinfunction "1_1") (pintype "passive"))
      (node (ref "C21") (pin "1") (pinfunction "1_1") (pintype "passive"))
      (node (ref "C23") (pin "1") (pinfunction "1_1") (pintype "passive"))
      (node (ref "C25") (pin "1") (pinfunction "1_1") (pintype "passive"))
      (node (ref "C30") (pin "1") (pinfunction "1_1") (pintype "passive"))
      (node (ref "C38") (pin "1") (pinfunction "1_1") (pintype "passive"))
      (node (ref "C40") (pin "1") (pinfunction "1_1") (pintype "passive"))
      (node (ref "C50") (pin "1") (pinfunction "1_1") (pintype "passive"))
      (node (ref "C53") (pin "1") (pinfunction "1_1") (pintype "passive"))
      (node (ref "C54") (pin "1") (pinfunction "1_1") (pintype "passive"))
      (node (ref "C55") (pin "1") (pinfunction "1_1") (pintype "passive"))
      (node (ref "C56") (pin "1") (pinfunction "1_1") (pintype "passive"))
      (node (ref "C58") (pin "1") (pinfunction "1_1") (pintype "passive"))
      (node (ref "C59") (pin "1") (pinfunction "1_1") (pintype "passive"))
      (node (ref "C62") (pin "1") (pinfunction "1_1") (pintype "passive"))
      (node (ref "C65") (pin "1") (pinfunction "1_1") (pintype "passive"))
      (node (ref "C83") (pin "1") (pinfunction "1_1") (pintype "passive"))
      (node (ref "C84") (pin "1") (pinfunction "1_1") (pintype "passive"))
      (node (ref "CN1") (pin "B4") (pinfunction "GND_B_B4") (pintype "passive"))
      (node (ref "CN1") (pin "CH1") (pinfunction "CHASSIS1_CH1") (pintype "passive"))
      (node (ref "CN1") (pin "CH2") (pinfunction "CHASSIS2_CH2") (pintype "passive"))
      (node (ref "CN1") (pin "CH3") (pinfunction "CHASSIS3_CH3") (pintype "passive"))
      (node (ref "CN1") (pin "CH4") (pinfunction "CHASSIS4_CH4") (pintype "passive"))
      (node (ref "CN1") (pin "T4") (pinfunction "GND_T_T4") (pintype "passive"))
      (node (ref "CN5") (pin "B4") (pinfunction "GND_B_B4") (pintype "passive"))
      (node (ref "CN5") (pin "CH1") (pinfunction "CHASSIS1_CH1") (pintype "passive"))
      (node (ref "CN5") (pin "CH2") (pinfunction "CHASSIS2_CH2") (pintype "passive"))
      (node (ref "CN5") (pin "CH3") (pinfunction "CHASSIS3_CH3") (pintype "passive"))
      (node (ref "CN5") (pin "CH4") (pinfunction "CHASSIS4_CH4") (pintype "passive"))
      (node (ref "CN5") (pin "T4") (pinfunction "GND_T_T4") (pintype "passive"))
      (node (ref "CN7") (pin "A1") (pinfunction "GND1_A1") (pintype "passive"))
      (node (ref "CN7") (pin "A12") (pinfunction "GND2_A12") (pintype "passive"))
      (node (ref "CN7") (pin "B1") (pinfunction "GND3_B1") (pintype "passive"))
      (node (ref "CN7") (pin "B12") (pinfunction "GND4_B12") (pintype "passive"))
      (node (ref "CN7") (pin "SH1") (pinfunction "Shield1_SH1") (pintype "passive"))
      (node (ref "CN7") (pin "SH2") (pinfunction "Shield2_SH2") (pintype "passive"))
      (node (ref "CN7") (pin "SH3") (pinfunction "Shield3_SH3") (pintype "passive"))
      (node (ref "CN7") (pin "SH4") (pinfunction "Shield4_SH4") (pintype "passive"))
      (node (ref "LD1") (pin "2") (pintype "passive"))
      (node (ref "R129") (pin "1") (pinfunction "1_1") (pintype "passive"))
      (node (ref "R137") (pin "1") (pinfunction "1_1") (pintype "passive"))
      (node (ref "R139") (pin "1") (pinfunction "1_1") (pintype "passive"))
      (node (ref "R23") (pin "1") (pinfunction "1_1") (pintype "passive"))
      (node (ref "R24") (pin "1") (pinfunction "1_1") (pintype "passive"))
      (node (ref "R31") (pin "1") (pinfunction "1_1") (pintype "passive"))
      (node (ref "R36") (pin "1") (pinfunction "1_1") (pintype "passive"))
      (node (ref "R46") (pin "1") (pinfunction "1_1") (pintype "passive"))
      (node (ref "U1") (pin "3") (pinfunction "GND_3") (pintype "passive"))
      (node (ref "U11") (pin "1") (pinfunction "GND_1") (pintype "passive"))
      (node (ref "U12") (pin "10") (pinfunction "GND_10") (pintype "passive"))
      (node (ref "U12") (pin "22") (pinfunction "VSYS_22") (pintype "passive"))
      (node (ref "U12") (pin "ep") (pinfunction "EP_ep") (pintype "passive"))
      (node (ref "U17") (pin "3") (pinfunction "GND_3") (pintype "passive"))
      (node (ref "U2") (pin "3") (pinfunction "GND_3") (pintype "passive"))
      (node (ref "U24") (pin "2") (pinfunction "GND_2") (pintype "passive"))
      (node (ref "U25") (pin "2") (pinfunction "GND_2") (pintype "passive"))
      (node (ref "U27") (pin "2") (pinfunction "GND_2") (pintype "passive"))
      (node (ref "U28") (pin "2") (pinfunction "GND_2") (pintype "passive"))
      (node (ref "U29") (pin "3") (pinfunction "GND_3") (pintype "passive"))
      (node (ref "U3") (pin "1") (pinfunction "GND_1") (pintype "passive"))
      (node (ref "U30") (pin "2") (pinfunction "GND_2") (pintype "passive"))
      (node (ref "U6") (pin "3") (pinfunction "GND_3") (pintype "passive"))
      (node (ref "U7") (pin "11") (pinfunction "TEST_11") (pintype "input"))
      (node (ref "U7") (pin "37") (pinfunction "VSS(FLAG)_37") (pintype "power_in"))
      (node (ref "U9") (pin "3") (pinfunction "GND_3") (pintype "passive"))
      (node (ref "X1") (pin "2") (pinfunction "2_2") (pintype "passive"))
      (node (ref "X1") (pin "4") (pinfunction "4_4") (pintype "passive"))
    )
    (net (code "39") (name "Net-(C66-Pad2)") (class "Default")
      (node (ref "C66") (pin "2") (pinfunction "2_2") (pintype "passive"))
      (node (ref "R42") (pin "2") (pinfunction "2_2") (pintype "passive"))
      (node (ref "T1") (pin "1") (pinfunction "S_1") (pintype "passive"))
      (node (ref "T1") (pin "2") (pinfunction "S_2") (pintype "passive"))
      (node (ref "T1") (pin "3") (pinfunction "S_3") (pintype "passive"))
      (node (ref "T2") (pin "1") (pinfunction "S_1") (pintype "passive"))
      (node (ref "T2") (pin "2") (pinfunction "S_2") (pintype "passive"))
      (node (ref "T2") (pin "3") (pinfunction "S_3") (pintype "passive"))
    )
    (net (code "40") (name "Net-(CN1-VBUS_B)") (class "Default")
      (node (ref "C117") (pin "2") (pinfunction "2_2") (pintype "passive"))
      (node (ref "C118") (pin "2") (pinfunction "2_2") (pintype "passive"))
      (node (ref "CN1") (pin "B1") (pinfunction "VBUS_B_B1") (pintype "passive"))
      (node (ref "U24") (pin "1") (pinfunction "IO1_1") (pintype "passive"))
      (node (ref "U3") (pin "6") (pinfunction "OUT2_6") (pintype "passive"))
    )
    (net (code "41") (name "Net-(CN1-VBUS_T)") (class "Default")
      (node (ref "C123") (pin "2") (pinfunction "2_2") (pintype "passive"))
      (node (ref "C124") (pin "2") (pinfunction "2_2") (pintype "passive"))
      (node (ref "CN1") (pin "T1") (pinfunction "VBUS_T_T1") (pintype "passive"))
      (node (ref "U25") (pin "1") (pinfunction "IO1_1") (pintype "passive"))
      (node (ref "U3") (pin "7") (pinfunction "OUT1_7") (pintype "passive"))
    )
    (net (code "42") (name "Net-(CN5-VBUS_B)") (class "Default")
      (node (ref "C133") (pin "2") (pinfunction "2_2") (pintype "passive"))
      (node (ref "C136") (pin "2") (pinfunction "2_2") (pintype "passive"))
      (node (ref "CN5") (pin "B1") (pinfunction "VBUS_B_B1") (pintype "passive"))
      (node (ref "U11") (pin "6") (pinfunction "OUT2_6") (pintype "passive"))
      (node (ref "U27") (pin "1") (pinfunction "IO1_1") (pintype "passive"))
    )
    (net (code "43") (name "Net-(CN5-VBUS_T)") (class "Default")
      (node (ref "C137") (pin "2") (pinfunction "2_2") (pintype "passive"))
      (node (ref "C138") (pin "2") (pinfunction "2_2") (pintype "passive"))
      (node (ref "CN5") (pin "T1") (pinfunction "VBUS_T_T1") (pintype "passive"))
      (node (ref "U11") (pin "7") (pinfunction "OUT1_7") (pintype "passive"))
      (node (ref "U28") (pin "1") (pinfunction "IO1_1") (pintype "passive"))
    )
    (net (code "44") (name "Net-(CN7-CC1)") (class "Default")
      (node (ref "C84") (pin "2") (pinfunction "2_2") (pintype "passive"))
      (node (ref "CN7") (pin "A5") (pinfunction "CC1_A5") (pintype "passive"))
      (node (ref "R34") (pin "2") (pinfunction "2_2") (pintype "passive"))
      (node (ref "U12") (pin "2") (pinfunction "CC1_2") (pintype "passive"))
      (node (ref "U17") (pin "1") (pinfunction "IO1_1") (pintype "passive"))
    )
    (net (code "45") (name "Net-(CN7-CC2)") (class "Default")
      (node (ref "C83") (pin "2") (pinfunction "2_2") (pintype "passive"))
      (node (ref "CN7") (pin "B5") (pinfunction "CC2_B5") (pintype "passive"))
      (node (ref "R35") (pin "2") (pinfunction "2_2") (pintype "passive"))
      (node (ref "U12") (pin "4") (pinfunction "CC2_4") (pintype "passive"))
      (node (ref "U17") (pin "2") (pinfunction "IO2_2") (pintype "passive"))
    )
    (net (code "46") (name "Net-(CN7-VBUS1)") (class "Default")
      (node (ref "C166") (pin "2") (pinfunction "2_2") (pintype "passive"))
      (node (ref "C167") (pin "2") (pinfunction "2_2") (pintype "passive"))
      (node (ref "CN7") (pin "A4") (pinfunction "VBUS1_A4") (pintype "passive"))
      (node (ref "CN7") (pin "A9") (pinfunction "VBUS2_A9") (pintype "passive"))
      (node (ref "CN7") (pin "B4") (pinfunction "VBUS3_B4") (pintype "passive"))
      (node (ref "CN7") (pin "B9") (pinfunction "VBUS4_B9") (pintype "passive"))
      (node (ref "R150") (pin "1") (pinfunction "1_1") (pintype "passive"))
      (node (ref "U30") (pin "1") (pinfunction "IO1_1") (pintype "passive"))
    )
    (net (code "47") (name "Net-(LD1-Pad1)") (class "Default")
      (node (ref "LD1") (pin "1") (pintype "passive"))
      (node (ref "R21") (pin "1") (pinfunction "1_1") (pintype "passive"))
    )
    (net (code "48") (name "Net-(T1-G)") (class "Default")
      (node (ref "C66") (pin "1") (pinfunction "1_1") (pintype "passive"))
      (node (ref "R42") (pin "1") (pinfunction "1_1") (pintype "passive"))
      (node (ref "R43") (pin "1") (pinfunction "1_1") (pintype "passive"))
      (node (ref "T1") (pin "4") (pinfunction "G_4") (pintype "passive"))
      (node (ref "T2") (pin "4") (pinfunction "G_4") (pintype "passive"))
    )
    (net (code "49") (name "Net-(U7-CRFILT)") (class "Default")
      (node (ref "C25") (pin "2") (pinfunction "2_2") (pintype "passive"))
      (node (ref "U7") (pin "14") (pinfunction "CRFILT_14") (pintype "power_in"))
    )
    (net (code "50") (name "Net-(U7-HS_IND{slash}CFG_SEL1)") (class "Default")
      (node (ref "R139") (pin "2") (pinfunction "2_2") (pintype "passive"))
      (node (ref "R140") (pin "1") (pinfunction "1_1") (pintype "passive"))
      (node (ref "U7") (pin "25") (pinfunction "HS_IND/CFG_SEL1_25") (pintype "passive"))
    )
    (net (code "51") (name "Net-(U7-PLLFILT)") (class "Default")
      (node (ref "C53") (pin "2") (pinfunction "2_2") (pintype "passive"))
      (node (ref "U7") (pin "34") (pinfunction "PLLFILT_34") (pintype "power_in"))
    )
    (net (code "52") (name "Net-(U7-RBIAS)") (class "Default")
      (node (ref "R24") (pin "2") (pinfunction "2_2") (pintype "passive"))
      (node (ref "U7") (pin "35") (pinfunction "RBIAS_35") (pintype "passive"))
    )
    (net (code "53") (name "Net-(U7-SCL{slash}SMBCLK{slash}CFG_SEL0)") (class "Default")
      (node (ref "R134") (pin "1") (pinfunction "1_1") (pintype "passive"))
      (node (ref "R137") (pin "2") (pinfunction "2_2") (pintype "passive"))
      (node (ref "SB8") (pin "2") (pinfunction "2_2") (pintype "passive"))
      (node (ref "U7") (pin "24") (pinfunction "SCL/SMBCLK/CFG_SEL0_24") (pintype "bidirectional"))
    )
    (net (code "54") (name "Net-(U7-SDA{slash}SMBDATA{slash}NON_REM1)") (class "Default")
      (node (ref "R127") (pin "1") (pinfunction "1_1") (pintype "passive"))
      (node (ref "R129") (pin "2") (pinfunction "2_2") (pintype "passive"))
      (node (ref "SB7") (pin "2") (pinfunction "2_2") (pintype "passive"))
      (node (ref "U7") (pin "22") (pinfunction "SDA/SMBDATA/NON_REM1_22") (pintype "bidirectional"))
    )
    (net (code "55") (name "Net-(U7-SUSP_IND{slash}L_PWR{slash}NON_REM0)") (class "Default")
      (node (ref "R21") (pin "2") (pinfunction "2_2") (pintype "passive"))
      (node (ref "R23") (pin "2") (pinfunction "2_2") (pintype "passive"))
      (node (ref "U7") (pin "28") (pinfunction "SUSP_IND/L_PWR/NON_REM0_28") (pintype "passive"))
    )
    (net (code "56") (name "Net-(U7-VBUS_DET)") (class "Default")
      (node (ref "R18") (pin "1") (pinfunction "1_1") (pintype "passive"))
      (node (ref "U7") (pin "27") (pinfunction "VBUS_DET_27") (pintype "passive"))
    )
    (net (code "57") (name "Net-(U7-XTAL1{slash}CKIN)") (class "Default")
      (node (ref "C59") (pin "2") (pinfunction "2_2") (pintype "passive"))
      (node (ref "U7") (pin "33") (pinfunction "XTAL1/CKIN_33") (pintype "input"))
      (node (ref "X1") (pin "1") (pinfunction "1_1") (pintype "passive"))
    )
    (net (code "58") (name "Net-(U7-XTAL2{slash}CKIN_EN)") (class "Default")
      (node (ref "C58") (pin "2") (pinfunction "2_2") (pintype "passive"))
      (node (ref "U7") (pin "32") (pinfunction "XTAL2/CKIN_EN_32") (pintype "output"))
      (node (ref "X1") (pin "3") (pinfunction "3_3") (pintype "passive"))
    )
    (net (code "59") (name "Net-(U7-~{RESET})") (class "Default")
      (node (ref "R600") (pin "2") (pinfunction "2_2") (pintype "passive"))
      (node (ref "U7") (pin "26") (pinfunction "~{RESET}_26") (pintype "input"))
    )
    (net (code "60") (name "Net-(U11-IN)") (class "Default")
      (node (ref "L8") (pin "2") (pinfunction "2_2") (pintype "passive"))
      (node (ref "U11") (pin "2") (pinfunction "IN_2") (pintype "passive"))
      (node (ref "U3") (pin "2") (pinfunction "IN_2") (pintype "passive"))
    )
    (net (code "61") (name "Net-(U12-ADDR0)") (class "Default")
      (node (ref "R46") (pin "2") (pinfunction "2_2") (pintype "passive"))
      (node (ref "U12") (pin "13") (pinfunction "ADDR0_13") (pintype "passive"))
    )
    (net (code "62") (name "Net-(U12-ATTACH)") (class "Default")
      (node (ref "TP16") (pin "1") (pinfunction "1_1") (pintype "passive"))
      (node (ref "U12") (pin "12") (pinfunction "ATTACH_12") (pintype "passive"))
    )
    (net (code "63") (name "Net-(U12-CC1DB)") (class "Default")
      (node (ref "R34") (pin "1") (pinfunction "1_1") (pintype "passive"))
      (node (ref "U12") (pin "1") (pinfunction "CC1DB_1") (pintype "passive"))
    )
    (net (code "64") (name "Net-(U12-CC2DB)") (class "Default")
      (node (ref "R35") (pin "1") (pinfunction "1_1") (pintype "passive"))
      (node (ref "U12") (pin "5") (pinfunction "CC2DB_5") (pintype "passive"))
    )
    (net (code "65") (name "Net-(U12-DEBUG1)") (class "Default")
      (node (ref "TP17") (pin "1") (pinfunction "1_1") (pintype "passive"))
      (node (ref "U12") (pin "14") (pinfunction "DEBUG1_14") (pintype "passive"))
    )
    (net (code "66") (name "Net-(U12-DEBUG2)") (class "Default")
      (node (ref "TP18") (pin "1") (pinfunction "1_1") (pintype "passive"))
      (node (ref "U12") (pin "15") (pinfunction "DEBUG2_15") (pintype "passive"))
    )
    (net (code "67") (name "Net-(U12-RESET)") (class "Default")
      (node (ref "R36") (pin "2") (pinfunction "2_2") (pintype "passive"))
      (node (ref "U12") (pin "6") (pinfunction "RESET_6") (pintype "passive"))
    )
    (net (code "68") (name "Net-(U12-VBUS_EN_SRC)") (class "Default")
      (node (ref "R43") (pin "2") (pinfunction "2_2") (pintype "passive"))
      (node (ref "U12") (pin "20") (pinfunction "VBUS_EN_SRC_20") (pintype "passive"))
    )
    (net (code "69") (name "Net-(U12-VBUS_SENSE)") (class "Default")
      (node (ref "R150") (pin "2") (pinfunction "2_2") (pintype "passive"))
      (node (ref "T2") (pin "5") (pinfunction "D_5") (pintype "passive"))
      (node (ref "T2") (pin "6") (pinfunction "D_6") (pintype "passive"))
      (node (ref "T2") (pin "7") (pinfunction "D_7") (pintype "passive"))
      (node (ref "T2") (pin "8") (pinfunction "D_8") (pintype "passive"))
      (node (ref "U12") (pin "18") (pinfunction "VBUS_SENSE_18") (pintype "passive"))
    )
    (net (code "70") (name "Net-(U12-VBUS_VALID)") (class "Default")
      (node (ref "TP15") (pin "1") (pinfunction "1_1") (pintype "passive"))
      (node (ref "U12") (pin "11") (pinfunction "VBUS_VALID_11") (pintype "passive"))
    )
    (net (code "71") (name "Net-(U12-VCONN)") (class "Default")
      (node (ref "R31") (pin "2") (pinfunction "2_2") (pintype "passive"))
      (node (ref "R32") (pin "1") (pinfunction "1_1") (pintype "passive"))
      (node (ref "U12") (pin "3") (pinfunction "VCONN_3") (pintype "passive"))
    )
    (net (code "72") (name "Net-(U12-VREG_1V2)") (class "Default")
      (node (ref "C65") (pin "2") (pinfunction "2_2") (pintype "passive"))
      (node (ref "U12") (pin "21") (pinfunction "VREG_1V2_21") (pintype "passive"))
    )
    (net (code "73") (name "Net-(U12-VREG_2V7)") (class "Default")
      (node (ref "C62") (pin "2") (pinfunction "2_2") (pintype "passive"))
      (node (ref "U12") (pin "23") (pinfunction "VREG_2V7_23") (pintype "passive"))
    )
    (net (code "74") (name "unconnected-(CN7-RX1+-PadB11)") (class "Default")
      (node (ref "CN7") (pin "B11") (pinfunction "RX1+_B11") (pintype "passive+no_connect"))
    )
    (net (code "75") (name "unconnected-(CN7-RX1--PadB10)") (class "Default")
      (node (ref "CN7") (pin "B10") (pinfunction "RX1-_B10") (pintype "passive+no_connect"))
    )
    (net (code "76") (name "unconnected-(CN7-RX2+-PadA11)") (class "Default")
      (node (ref "CN7") (pin "A11") (pinfunction "RX2+_A11") (pintype "passive+no_connect"))
    )
    (net (code "77") (name "unconnected-(CN7-RX2--PadA10)") (class "Default")
      (node (ref "CN7") (pin "A10") (pinfunction "RX2-_A10") (pintype "passive+no_connect"))
    )
    (net (code "78") (name "unconnected-(CN7-SBU1-PadA8)") (class "Default")
      (node (ref "CN7") (pin "A8") (pinfunction "SBU1_A8") (pintype "passive+no_connect"))
    )
    (net (code "79") (name "unconnected-(CN7-SBU2-PadB8)") (class "Default")
      (node (ref "CN7") (pin "B8") (pinfunction "SBU2_B8") (pintype "passive+no_connect"))
    )
    (net (code "80") (name "unconnected-(CN7-TX1+-PadA2)") (class "Default")
      (node (ref "CN7") (pin "A2") (pinfunction "TX1+_A2") (pintype "passive+no_connect"))
    )
    (net (code "81") (name "unconnected-(CN7-TX1--PadA3)") (class "Default")
      (node (ref "CN7") (pin "A3") (pinfunction "TX1-_A3") (pintype "passive+no_connect"))
    )
    (net (code "82") (name "unconnected-(CN7-TX2+-PadB2)") (class "Default")
      (node (ref "CN7") (pin "B2") (pinfunction "TX2+_B2") (pintype "passive+no_connect"))
    )
    (net (code "83") (name "unconnected-(CN7-TX2--PadB3)") (class "Default")
      (node (ref "CN7") (pin "B3") (pinfunction "TX2-_B3") (pintype "passive+no_connect"))
    )
    (net (code "84") (name "unconnected-(U1-NC-Pad4)") (class "Default")
      (node (ref "U1") (pin "4") (pinfunction "NC_4") (pintype "passive+no_connect"))
    )
    (net (code "85") (name "unconnected-(U2-NC-Pad4)") (class "Default")
      (node (ref "U2") (pin "4") (pinfunction "NC_4") (pintype "passive+no_connect"))
    )
    (net (code "86") (name "unconnected-(U6-NC-Pad4)") (class "Default")
      (node (ref "U6") (pin "4") (pinfunction "NC_4") (pintype "passive+no_connect"))
    )
    (net (code "87") (name "unconnected-(U9-NC-Pad4)") (class "Default")
      (node (ref "U9") (pin "4") (pinfunction "NC_4") (pintype "passive+no_connect"))
    )
    (net (code "88") (name "unconnected-(U12-A_B_SIDE-Pad17)") (class "Default")
      (node (ref "U12") (pin "17") (pinfunction "A_B_SIDE_17") (pintype "passive+no_connect"))
    )
    (net (code "89") (name "unconnected-(U12-NC-Pad16)") (class "Default")
      (node (ref "U12") (pin "16") (pinfunction "NC_16") (pintype "passive+no_connect"))
    )
    (net (code "90") (name "unconnected-(U12-VBUS_EN_SNK-Pad19)") (class "Default")
      (node (ref "U12") (pin "19") (pinfunction "VBUS_EN_SNK_19") (pintype "passive+no_connect"))
    )
    (net (code "91") (name "unconnected-(U29-NC-Pad4)") (class "Default")
      (node (ref "U29") (pin "4") (pinfunction "NC_4") (pintype "passive+no_connect"))
    )
  )
)
